# grid-rfduino_v3.net
KiCad netlist of a schematic drawn in EAGLE
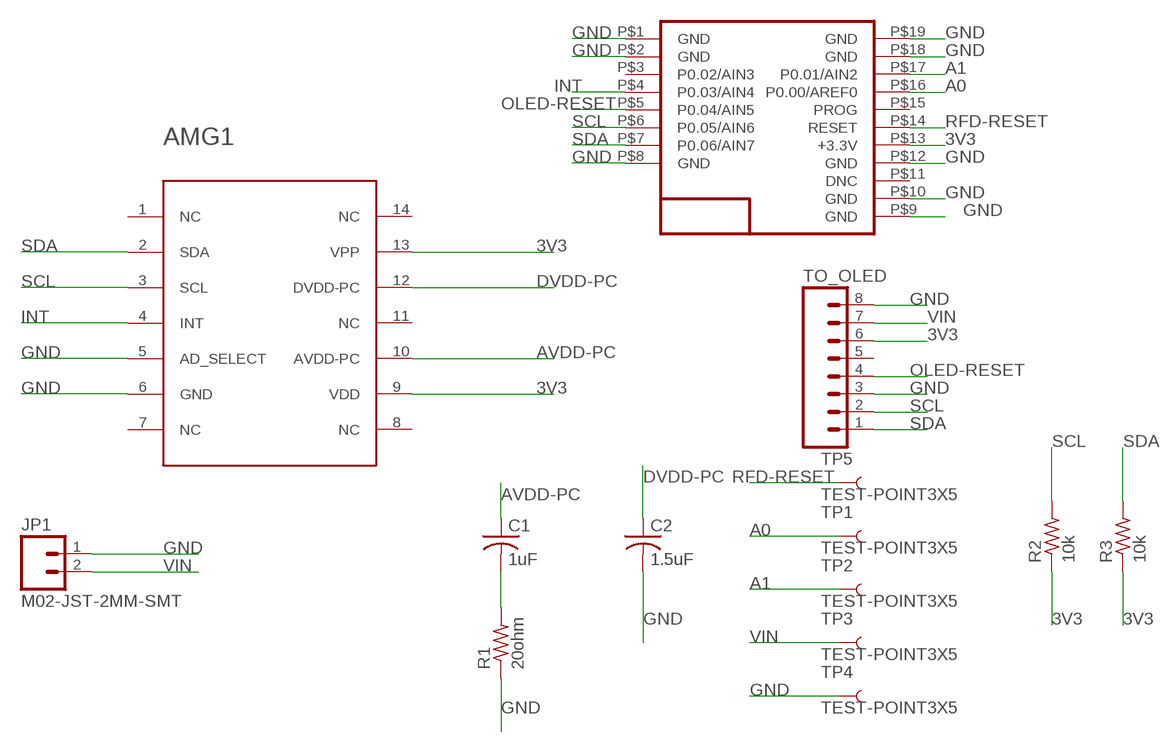
[diagram p0: schematic, sheet 1]

(export (version "E")
  (design (tool "Eeschema 10.0.6"))
  (components
    (comp (ref "AMG1")
      (value "AMG8831")
      (footprint "eagle-import:AMG8831")
      (libsource (lib "eagle-import") (part "AMG8831"))
    )
    (comp (ref "C1")
      (value "1uF")
      (footprint "eagle-import:C0805")
      (libsource (lib "eagle-import") (part "C-USC0805"))
    )
    (comp (ref "C2")
      (value "1.5uF")
      (footprint "eagle-import:C0805")
      (libsource (lib "eagle-import") (part "C-USC0805"))
    )
    (comp (ref "JP1")
      (value "M02-JST-2MM-SMT")
      (footprint "eagle-import:JST-2-SMD")
      (libsource (lib "eagle-import") (part "M02-JST-2MM-SMT"))
    )
    (comp (ref "R1")
      (value "20ohm")
      (footprint "eagle-import:M0805")
      (libsource (lib "eagle-import") (part "R-US_M0805"))
    )
    (comp (ref "R2")
      (value "10k")
      (footprint "eagle-import:M0805")
      (libsource (lib "eagle-import") (part "R-US_M0805"))
    )
    (comp (ref "R3")
      (value "10k")
      (footprint "eagle-import:M0805")
      (libsource (lib "eagle-import") (part "R-US_M0805"))
    )
    (comp (ref "TO_OLED")
      (value "M08LOCK")
      (footprint "eagle-import:1X08_LOCK")
      (libsource (lib "eagle-import") (part "M08LOCK"))
    )
    (comp (ref "TP1")
      (value "TEST-POINT3X5")
      (footprint "eagle-import:PAD.03X.05")
      (libsource (lib "eagle-import") (part "TEST-POINT3X5"))
    )
    (comp (ref "TP2")
      (value "TEST-POINT3X5")
      (footprint "eagle-import:PAD.03X.05")
      (libsource (lib "eagle-import") (part "TEST-POINT3X5"))
    )
    (comp (ref "TP3")
      (value "TEST-POINT3X5")
      (footprint "eagle-import:PAD.03X.05")
      (libsource (lib "eagle-import") (part "TEST-POINT3X5"))
    )
    (comp (ref "TP4")
      (value "TEST-POINT3X5")
      (footprint "eagle-import:PAD.03X.05")
      (libsource (lib "eagle-import") (part "TEST-POINT3X5"))
    )
    (comp (ref "TP5")
      (value "TEST-POINT3X5")
      (footprint "eagle-import:PAD.03X.05")
      (libsource (lib "eagle-import") (part "TEST-POINT3X5"))
    )
    (comp (ref "U$1")
      (value "RFD22301")
      (footprint "eagle-import:RFD21733")
      (libsource (lib "eagle-import") (part "RFD22301"))
    )
  )
  (nets
    (net (code "1") (name "/3V3") (class "Default")
      (node (ref "AMG1") (pin "13") (pinfunction "VPP_13") (pintype "power_in"))
      (node (ref "AMG1") (pin "9") (pinfunction "VDD_9") (pintype "power_in"))
      (node (ref "R2") (pin "1") (pinfunction "1_1") (pintype "passive"))
      (node (ref "R3") (pin "1") (pinfunction "1_1") (pintype "passive"))
      (node (ref "TO_OLED") (pin "6") (pinfunction "6_6") (pintype "passive"))
      (node (ref "U$1") (pin "P$13") (pinfunction "+3.3V_P$13") (pintype "bidirectional"))
    )
    (net (code "2") (name "/A0") (class "Default")
      (node (ref "TP1") (pin "P$1") (pinfunction "1_P$1") (pintype "bidirectional"))
      (node (ref "U$1") (pin "P$16") (pinfunction "P0.00/AREF0_P$16") (pintype "bidirectional"))
    )
    (net (code "3") (name "/A1") (class "Default")
      (node (ref "TP2") (pin "P$1") (pinfunction "1_P$1") (pintype "bidirectional"))
      (node (ref "U$1") (pin "P$17") (pinfunction "P0.01/AIN2_P$17") (pintype "bidirectional"))
    )
    (net (code "4") (name "/AVDD-PC") (class "Default")
      (node (ref "AMG1") (pin "10") (pinfunction "AVDD-PC_10") (pintype "power_in"))
      (node (ref "C1") (pin "1") (pinfunction "1_1") (pintype "passive"))
    )
    (net (code "5") (name "/DVDD-PC") (class "Default")
      (node (ref "AMG1") (pin "12") (pinfunction "DVDD-PC_12") (pintype "power_in"))
      (node (ref "C2") (pin "1") (pinfunction "1_1") (pintype "passive"))
    )
    (net (code "6") (name "/GND") (class "Default")
      (node (ref "AMG1") (pin "5") (pinfunction "AD_SELECT_5") (pintype "bidirectional"))
      (node (ref "AMG1") (pin "6") (pinfunction "GND_6") (pintype "power_in"))
      (node (ref "C2") (pin "2") (pinfunction "2_2") (pintype "passive"))
      (node (ref "JP1") (pin "1") (pinfunction "2_1") (pintype "passive"))
      (node (ref "R1") (pin "1") (pinfunction "1_1") (pintype "passive"))
      (node (ref "TO_OLED") (pin "3") (pinfunction "3_3") (pintype "passive"))
      (node (ref "TO_OLED") (pin "8") (pinfunction "8_8") (pintype "passive"))
      (node (ref "TP4") (pin "P$1") (pinfunction "1_P$1") (pintype "bidirectional"))
      (node (ref "U$1") (pin "P$1") (pinfunction "GND_P$1") (pintype "bidirectional"))
      (node (ref "U$1") (pin "P$10") (pinfunction "GND_P$10") (pintype "bidirectional"))
      (node (ref "U$1") (pin "P$12") (pinfunction "GND_P$12") (pintype "bidirectional"))
      (node (ref "U$1") (pin "P$18") (pinfunction "GND_P$18") (pintype "bidirectional"))
      (node (ref "U$1") (pin "P$19") (pinfunction "GND_P$19") (pintype "bidirectional"))
      (node (ref "U$1") (pin "P$2") (pinfunction "GND_P$2") (pintype "bidirectional"))
      (node (ref "U$1") (pin "P$8") (pinfunction "GND_P$8") (pintype "bidirectional"))
      (node (ref "U$1") (pin "P$9") (pinfunction "GND_P$9") (pintype "bidirectional"))
    )
    (net (code "7") (name "/INT") (class "Default")
      (node (ref "AMG1") (pin "4") (pinfunction "INT_4") (pintype "bidirectional"))
      (node (ref "U$1") (pin "P$4") (pinfunction "P0.03/AIN4_P$4") (pintype "bidirectional"))
    )
    (net (code "8") (name "/OLED-RESET") (class "Default")
      (node (ref "TO_OLED") (pin "4") (pinfunction "4_4") (pintype "passive"))
      (node (ref "U$1") (pin "P$5") (pinfunction "P0.04/AIN5_P$5") (pintype "bidirectional"))
    )
    (net (code "9") (name "/RFD-RESET") (class "Default")
      (node (ref "TP5") (pin "P$1") (pinfunction "1_P$1") (pintype "bidirectional"))
      (node (ref "U$1") (pin "P$14") (pinfunction "RESET_P$14") (pintype "bidirectional"))
    )
    (net (code "10") (name "/SCL") (class "Default")
      (node (ref "AMG1") (pin "3") (pinfunction "SCL_3") (pintype "bidirectional"))
      (node (ref "R2") (pin "2") (pinfunction "2_2") (pintype "passive"))
      (node (ref "TO_OLED") (pin "2") (pinfunction "2_2") (pintype "passive"))
      (node (ref "U$1") (pin "P$6") (pinfunction "P0.05/AIN6_P$6") (pintype "bidirectional"))
    )
    (net (code "11") (name "/SDA") (class "Default")
      (node (ref "AMG1") (pin "2") (pinfunction "SDA_2") (pintype "bidirectional"))
      (node (ref "R3") (pin "2") (pinfunction "2_2") (pintype "passive"))
      (node (ref "TO_OLED") (pin "1") (pinfunction "1_1") (pintype "passive"))
      (node (ref "U$1") (pin "P$7") (pinfunction "P0.06/AIN7_P$7") (pintype "bidirectional"))
    )
    (net (code "12") (name "/VIN") (class "Default")
      (node (ref "JP1") (pin "2") (pinfunction "1_2") (pintype "passive"))
      (node (ref "TO_OLED") (pin "7") (pinfunction "7_7") (pintype "passive"))
      (node (ref "TP3") (pin "P$1") (pinfunction "1_P$1") (pintype "bidirectional"))
    )
    (net (code "13") (name "Net-(C1-Pad2)") (class "Default")
      (node (ref "C1") (pin "2") (pinfunction "2_2") (pintype "passive"))
      (node (ref "R1") (pin "2") (pinfunction "2_2") (pintype "passive"))
    )
    (net (code "14") (name "unconnected-(AMG1-NC-Pad1)") (class "Default")
      (node (ref "AMG1") (pin "1") (pinfunction "NC_1") (pintype "no_connect"))
    )
    (net (code "15") (name "unconnected-(AMG1-NC-Pad7)") (class "Default")
      (node (ref "AMG1") (pin "7") (pinfunction "NC_7") (pintype "no_connect"))
    )
    (net (code "16") (name "unconnected-(AMG1-NC-Pad8)") (class "Default")
      (node (ref "AMG1") (pin "8") (pinfunction "NC_8") (pintype "no_connect"))
    )
    (net (code "17") (name "unconnected-(AMG1-NC-Pad11)") (class "Default")
      (node (ref "AMG1") (pin "11") (pinfunction "NC_11") (pintype "no_connect"))
    )
    (net (code "18") (name "unconnected-(AMG1-NC-Pad14)") (class "Default")
      (node (ref "AMG1") (pin "14") (pinfunction "NC_14") (pintype "no_connect"))
    )
    (net (code "19") (name "unconnected-(TO_OLED-Pad5)") (class "Default")
      (node (ref "TO_OLED") (pin "5") (pinfunction "5_5") (pintype "passive"))
    )
    (net (code "20") (name "unconnected-(U$1-DNC-PadP$11)") (class "Default")
      (node (ref "U$1") (pin "P$11") (pinfunction "DNC_P$11") (pintype "bidirectional"))
    )
    (net (code "21") (name "unconnected-(U$1-P0.02{slash}AIN3-PadP$3)") (class "Default")
      (node (ref "U$1") (pin "P$3") (pinfunction "P0.02/AIN3_P$3") (pintype "bidirectional"))
    )
    (net (code "22") (name "unconnected-(U$1-PROG-PadP$15)") (class "Default")
      (node (ref "U$1") (pin "P$15") (pinfunction "PROG_P$15") (pintype "bidirectional"))
    )
  )
)
